# Adafruit_BMP183_Breakout.net
KiCad netlist of a schematic drawn in EAGLE
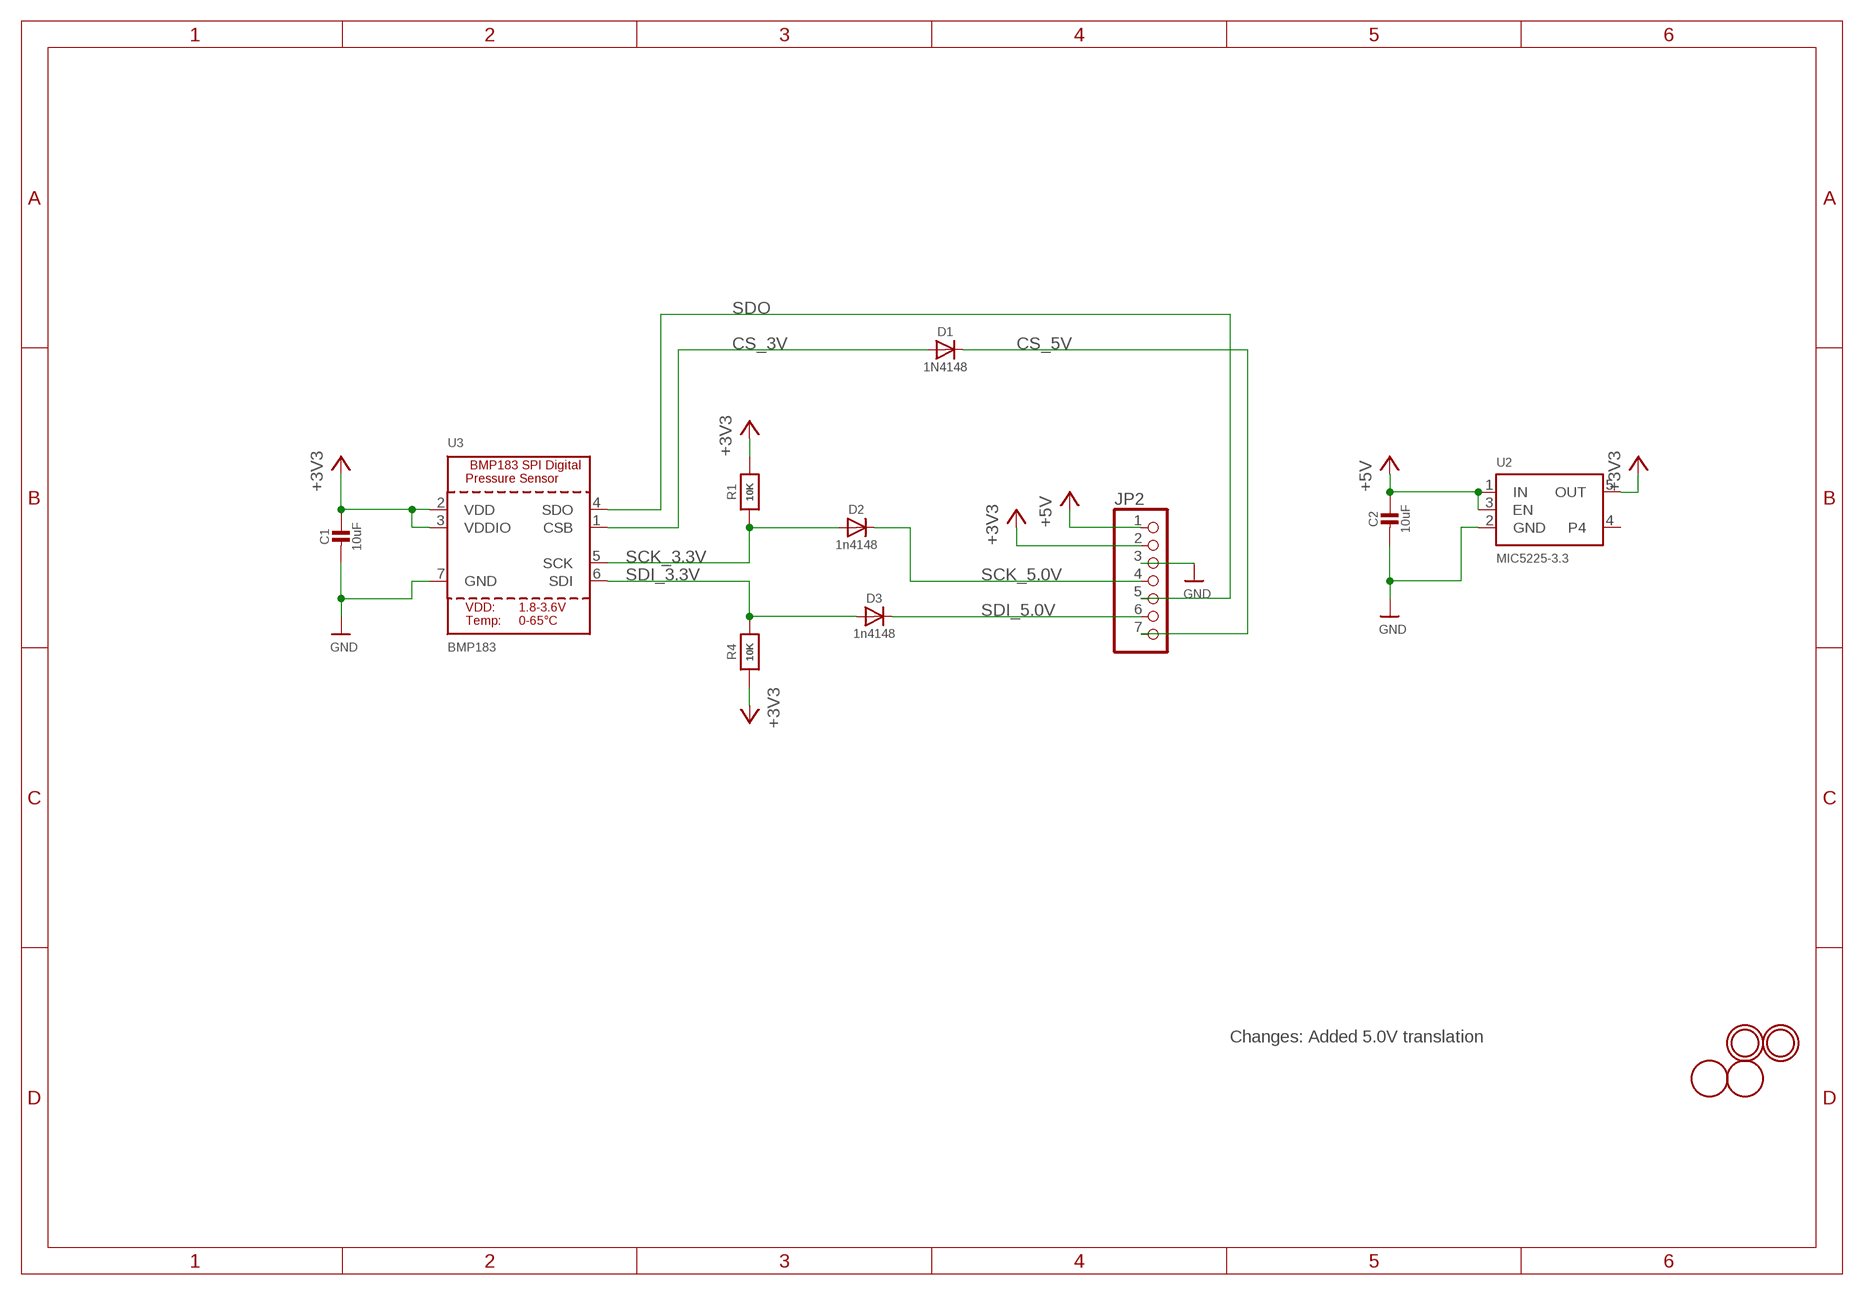
[diagram p0: schematic, sheet 1]

(export (version "E")
  (design (tool "Eeschema 10.0.6"))
  (components
    (comp (ref "C1")
      (value "10uF")
      (footprint "eagle-import:0805-NO")
      (libsource (lib "eagle-import") (part "CAP_CERAMIC0805-NOOUTLINE"))
    )
    (comp (ref "C2")
      (value "10uF")
      (footprint "eagle-import:0805-NO")
      (libsource (lib "eagle-import") (part "CAP_CERAMIC0805-NOOUTLINE"))
    )
    (comp (ref "D1")
      (value "1N4148")
      (footprint "eagle-import:SOD-323")
      (libsource (lib "eagle-import") (part "DIODESOD-323"))
    )
    (comp (ref "D2")
      (value "1n4148")
      (footprint "eagle-import:SOD-323")
      (libsource (lib "eagle-import") (part "DIODESOD-323"))
    )
    (comp (ref "D3")
      (value "1n4148")
      (footprint "eagle-import:SOD-323")
      (libsource (lib "eagle-import") (part "DIODESOD-323"))
    )
    (comp (ref "JP2")
      (value "HEADER-1X770MIL")
      (footprint "eagle-import:1X07_ROUND_70")
      (libsource (lib "eagle-import") (part "HEADER-1X770MIL"))
    )
    (comp (ref "R1")
      (value "10K")
      (footprint "eagle-import:0805-NO")
      (libsource (lib "eagle-import") (part "RESISTOR0805_NOOUTLINE"))
    )
    (comp (ref "R4")
      (value "10K")
      (footprint "eagle-import:0805-NO")
      (libsource (lib "eagle-import") (part "RESISTOR0805_NOOUTLINE"))
    )
    (comp (ref "U$5")
      (value "FIDUCIAL")
      (footprint "eagle-import:FIDUCIAL_1MM")
      (libsource (lib "eagle-import") (part "FIDUCIAL"))
    )
    (comp (ref "U$7")
      (value "MOUNTINGHOLE2.0")
      (footprint "eagle-import:MOUNTINGHOLE_2.0_PLATED")
      (libsource (lib "eagle-import") (part "MOUNTINGHOLE2.0"))
    )
    (comp (ref "U$8")
      (value "MOUNTINGHOLE2.0")
      (footprint "eagle-import:MOUNTINGHOLE_2.0_PLATED")
      (libsource (lib "eagle-import") (part "MOUNTINGHOLE2.0"))
    )
    (comp (ref "U$15")
      (value "FIDUCIAL")
      (footprint "eagle-import:FIDUCIAL_1MM")
      (libsource (lib "eagle-import") (part "FIDUCIAL"))
    )
    (comp (ref "U2")
      (value "MIC5225-3.3")
      (footprint "eagle-import:SOT23-5")
      (libsource (lib "eagle-import") (part "VREG_SOT23-5"))
    )
    (comp (ref "U3")
      (value "BMP183")
      (footprint "eagle-import:BMP18X_EXTENDED")
      (libsource (lib "eagle-import") (part "BMP183"))
    )
  )
  (nets
    (net (code "1") (name "+3V3") (class "Default")
      (node (ref "C1") (pin "1") (pinfunction "1_1") (pintype "passive"))
      (node (ref "JP2") (pin "2") (pinfunction "2_2") (pintype "passive"))
      (node (ref "R1") (pin "2") (pinfunction "2_2") (pintype "passive"))
      (node (ref "R4") (pin "1") (pinfunction "1_1") (pintype "passive"))
      (node (ref "U2") (pin "5") (pinfunction "OUT_5") (pintype "power_in"))
      (node (ref "U3") (pin "2") (pinfunction "VDD_2") (pintype "power_in"))
      (node (ref "U3") (pin "3") (pinfunction "VDDIO_3") (pintype "power_in"))
    )
    (net (code "2") (name "+5V") (class "Default")
      (node (ref "C2") (pin "1") (pinfunction "1_1") (pintype "passive"))
      (node (ref "JP2") (pin "1") (pinfunction "1_1") (pintype "passive"))
      (node (ref "U2") (pin "1") (pinfunction "IN_1") (pintype "power_in"))
      (node (ref "U2") (pin "3") (pinfunction "EN_3") (pintype "input"))
    )
    (net (code "3") (name "/CS_3V") (class "Default")
      (node (ref "D1") (pin "A") (pinfunction "A_A") (pintype "passive"))
      (node (ref "U3") (pin "1") (pinfunction "CSB_1") (pintype "input"))
    )
    (net (code "4") (name "/CS_5V") (class "Default")
      (node (ref "D1") (pin "C") (pinfunction "C_C") (pintype "passive"))
      (node (ref "JP2") (pin "7") (pinfunction "7_7") (pintype "passive"))
    )
    (net (code "5") (name "/SCK_3.3V") (class "Default")
      (node (ref "D2") (pin "A") (pinfunction "A_A") (pintype "passive"))
      (node (ref "R1") (pin "1") (pinfunction "1_1") (pintype "passive"))
      (node (ref "U3") (pin "5") (pinfunction "SCK_5") (pintype "input"))
    )
    (net (code "6") (name "/SCK_5.0V") (class "Default")
      (node (ref "D2") (pin "C") (pinfunction "C_C") (pintype "passive"))
      (node (ref "JP2") (pin "4") (pinfunction "4_4") (pintype "passive"))
    )
    (net (code "7") (name "/SDI_3.3V") (class "Default")
      (node (ref "D3") (pin "A") (pinfunction "A_A") (pintype "passive"))
      (node (ref "R4") (pin "2") (pinfunction "2_2") (pintype "passive"))
      (node (ref "U3") (pin "6") (pinfunction "SDI_6") (pintype "input"))
    )
    (net (code "8") (name "/SDI_5.0V") (class "Default")
      (node (ref "D3") (pin "C") (pinfunction "C_C") (pintype "passive"))
      (node (ref "JP2") (pin "6") (pinfunction "6_6") (pintype "passive"))
    )
    (net (code "9") (name "/SDO") (class "Default")
      (node (ref "JP2") (pin "5") (pinfunction "5_5") (pintype "passive"))
      (node (ref "U3") (pin "4") (pinfunction "SDO_4") (pintype "output"))
    )
    (net (code "10") (name "GND") (class "Default")
      (node (ref "C1") (pin "2") (pinfunction "2_2") (pintype "passive"))
      (node (ref "C2") (pin "2") (pinfunction "2_2") (pintype "passive"))
      (node (ref "JP2") (pin "3") (pinfunction "3_3") (pintype "passive"))
      (node (ref "U2") (pin "2") (pinfunction "GND_2") (pintype "power_in"))
      (node (ref "U3") (pin "7") (pinfunction "GND_7") (pintype "power_in"))
    )
    (net (code "11") (name "unconnected-(U2-P4-Pad4)") (class "Default")
      (node (ref "U2") (pin "4") (pinfunction "P4_4") (pintype "bidirectional"))
    )
  )
)
